# SaltwatersEchoCore.net
KiCad netlist of a schematic drawn in EAGLE
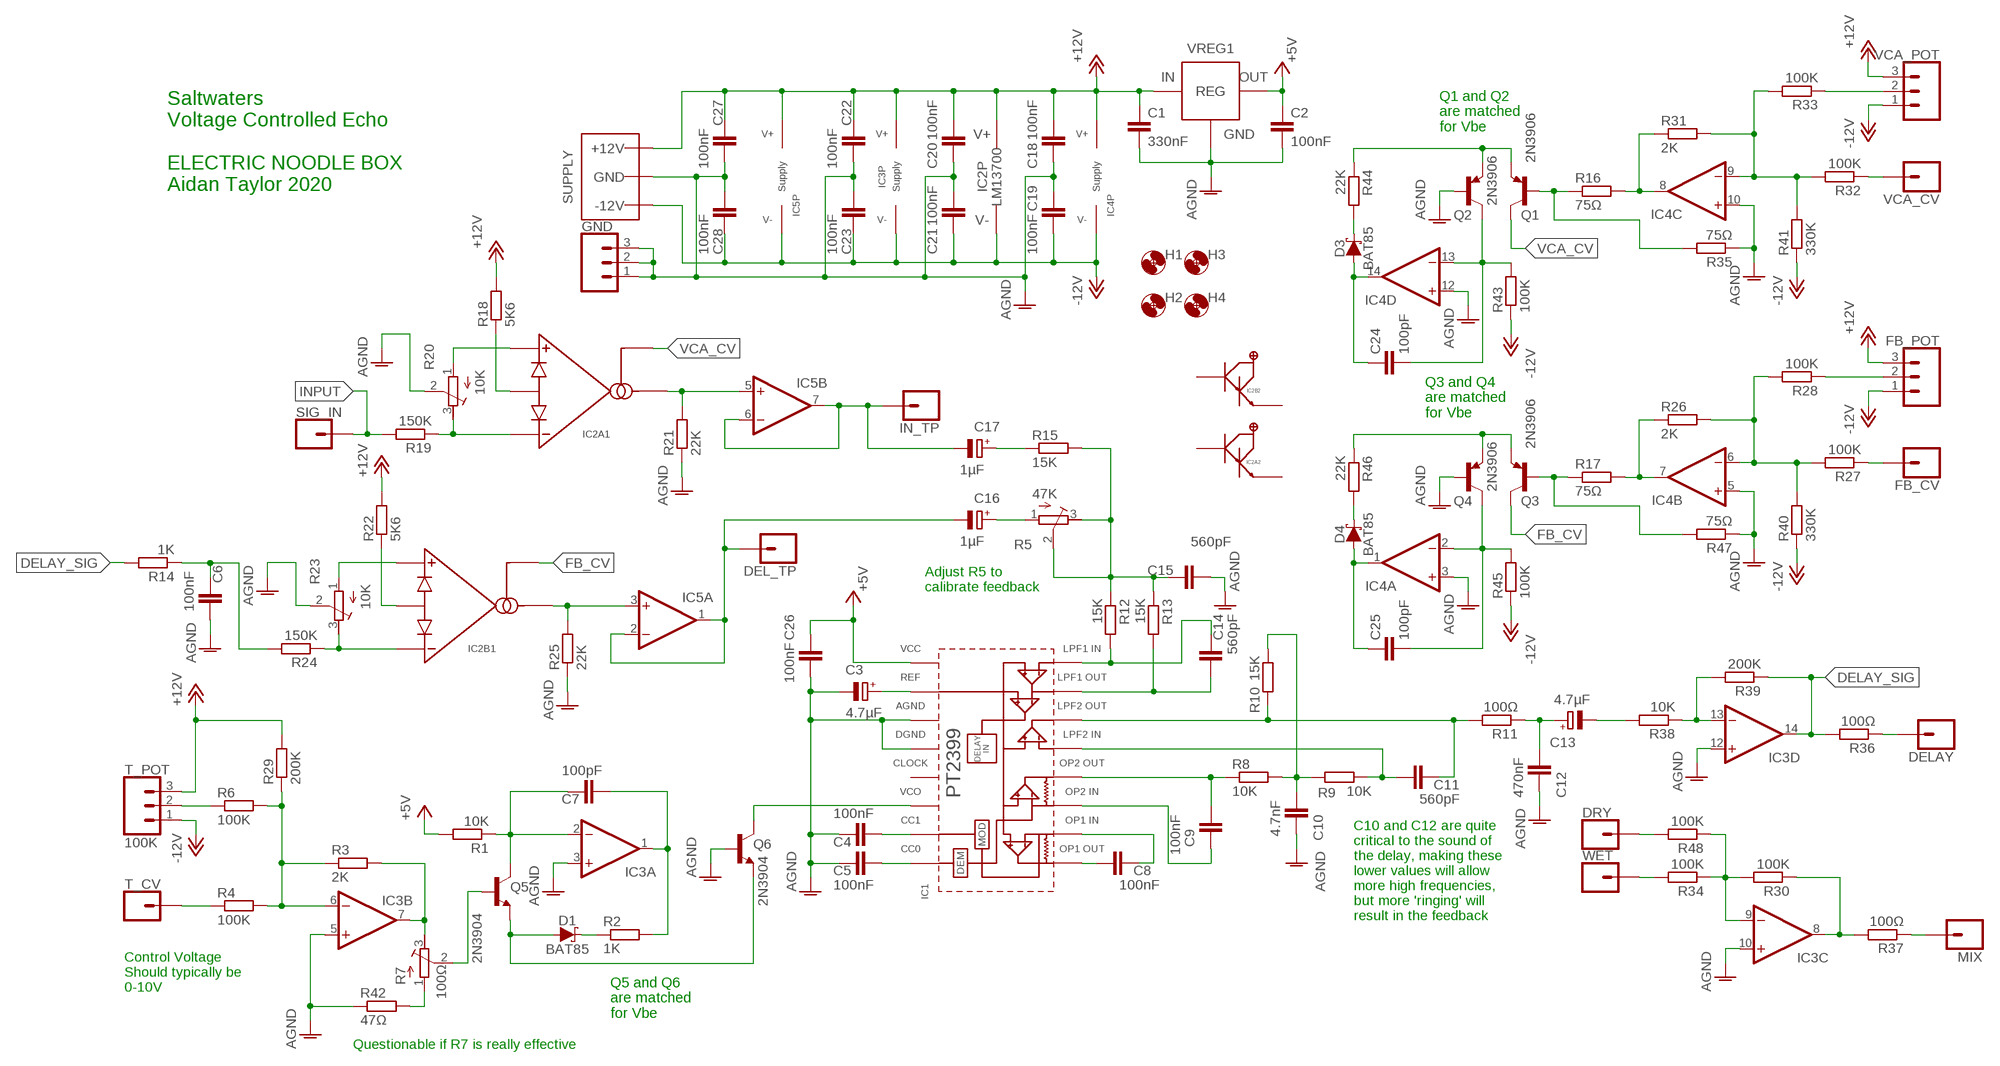
[diagram p0: schematic, sheet 1]

(export (version "E")
  (design (tool "Eeschema 10.0.6"))
  (components
    (comp (ref "C1")
      (value "330nF")
      (footprint "eagle-import:C050-025X075")
      (libsource (lib "eagle-import") (part "C-EU050-025X075"))
    )
    (comp (ref "C2")
      (value "100nF")
      (footprint "eagle-import:C050-025X075")
      (libsource (lib "eagle-import") (part "C-EU050-025X075"))
    )
    (comp (ref "C3")
      (value "4.7µF")
      (footprint "eagle-import:E2-5")
      (libsource (lib "eagle-import") (part "CPOL-EUE2-5"))
    )
    (comp (ref "C4")
      (value "100nF")
      (footprint "eagle-import:C050-025X075")
      (libsource (lib "eagle-import") (part "C-EU050-025X075"))
    )
    (comp (ref "C5")
      (value "100nF")
      (footprint "eagle-import:C050-025X075")
      (libsource (lib "eagle-import") (part "C-EU050-025X075"))
    )
    (comp (ref "C6")
      (value "100nF")
      (footprint "eagle-import:C050-025X075")
      (libsource (lib "eagle-import") (part "C-EU050-025X075"))
    )
    (comp (ref "C7")
      (value "100pF")
      (footprint "eagle-import:C050-025X075")
      (libsource (lib "eagle-import") (part "C-EU050-025X075"))
    )
    (comp (ref "C8")
      (value "100nF")
      (footprint "eagle-import:C050-025X075")
      (libsource (lib "eagle-import") (part "C-EU050-025X075"))
    )
    (comp (ref "C9")
      (value "100nF")
      (footprint "eagle-import:C050-025X075")
      (libsource (lib "eagle-import") (part "C-EU050-025X075"))
    )
    (comp (ref "C10")
      (value "4.7nF")
      (footprint "eagle-import:C050-025X075")
      (libsource (lib "eagle-import") (part "C-EU050-025X075"))
    )
    (comp (ref "C11")
      (value "560pF")
      (footprint "eagle-import:C050-025X075")
      (libsource (lib "eagle-import") (part "C-EU050-025X075"))
    )
    (comp (ref "C12")
      (value "470nF")
      (footprint "eagle-import:C050-025X075")
      (libsource (lib "eagle-import") (part "C-EU050-025X075"))
    )
    (comp (ref "C13")
      (value "4.7µF")
      (footprint "eagle-import:E2-5")
      (libsource (lib "eagle-import") (part "CPOL-EUE2-5"))
    )
    (comp (ref "C14")
      (value "560pF")
      (footprint "eagle-import:C050-025X075")
      (libsource (lib "eagle-import") (part "C-EU050-025X075"))
    )
    (comp (ref "C15")
      (value "560pF")
      (footprint "eagle-import:C050-025X075")
      (libsource (lib "eagle-import") (part "C-EU050-025X075"))
    )
    (comp (ref "C16")
      (value "1µF")
      (footprint "eagle-import:E2-5")
      (libsource (lib "eagle-import") (part "CPOL-EUE2-5"))
    )
    (comp (ref "C17")
      (value "1µF")
      (footprint "eagle-import:E2-5")
      (libsource (lib "eagle-import") (part "CPOL-EUE2-5"))
    )
    (comp (ref "C18")
      (value "100nF")
      (footprint "eagle-import:C050-025X075")
      (libsource (lib "eagle-import") (part "C-EU050-025X075"))
    )
    (comp (ref "C19")
      (value "100nF")
      (footprint "eagle-import:C050-025X075")
      (libsource (lib "eagle-import") (part "C-EU050-025X075"))
    )
    (comp (ref "C20")
      (value "100nF")
      (footprint "eagle-import:C050-025X075")
      (libsource (lib "eagle-import") (part "C-EU050-025X075"))
    )
    (comp (ref "C21")
      (value "100nF")
      (footprint "eagle-import:C050-025X075")
      (libsource (lib "eagle-import") (part "C-EU050-025X075"))
    )
    (comp (ref "C22")
      (value "100nF")
      (footprint "eagle-import:C050-025X075")
      (libsource (lib "eagle-import") (part "C-EU050-025X075"))
    )
    (comp (ref "C23")
      (value "100nF")
      (footprint "eagle-import:C050-025X075")
      (libsource (lib "eagle-import") (part "C-EU050-025X075"))
    )
    (comp (ref "C24")
      (value "100pF")
      (footprint "eagle-import:C050-025X075")
      (libsource (lib "eagle-import") (part "C-EU050-025X075"))
    )
    (comp (ref "C25")
      (value "100pF")
      (footprint "eagle-import:C050-025X075")
      (libsource (lib "eagle-import") (part "C-EU050-025X075"))
    )
    (comp (ref "C26")
      (value "100nF")
      (footprint "eagle-import:C050-025X075")
      (libsource (lib "eagle-import") (part "C-EU050-025X075"))
    )
    (comp (ref "C27")
      (value "100nF")
      (footprint "eagle-import:C050-025X075")
      (libsource (lib "eagle-import") (part "C-EU050-025X075"))
    )
    (comp (ref "C28")
      (value "100nF")
      (footprint "eagle-import:C050-025X075")
      (libsource (lib "eagle-import") (part "C-EU050-025X075"))
    )
    (comp (ref "D1")
      (value "BAT85")
      (footprint "eagle-import:DO35-7")
      (libsource (lib "eagle-import") (part "SCHOTTKY_DO35"))
    )
    (comp (ref "D3")
      (value "BAT85")
      (footprint "eagle-import:DO35-7")
      (libsource (lib "eagle-import") (part "SCHOTTKY_DO35"))
    )
    (comp (ref "D4")
      (value "BAT85")
      (footprint "eagle-import:DO35-7")
      (libsource (lib "eagle-import") (part "SCHOTTKY_DO35"))
    )
    (comp (ref "DELAY")
      (value "1XWIREPAD")
      (footprint "eagle-import:1X01")
      (libsource (lib "eagle-import") (part "1XWIREPAD"))
    )
    (comp (ref "DEL_TP")
      (value "1XWIREPAD")
      (footprint "eagle-import:1X01")
      (libsource (lib "eagle-import") (part "1XWIREPAD"))
    )
    (comp (ref "DRY")
      (value "1XWIREPAD")
      (footprint "eagle-import:1X01")
      (libsource (lib "eagle-import") (part "1XWIREPAD"))
    )
    (comp (ref "FB_CV")
      (value "1XWIREPAD")
      (footprint "eagle-import:1X01")
      (libsource (lib "eagle-import") (part "1XWIREPAD"))
    )
    (comp (ref "FB_POT")
      (value "3XWIREPAD")
      (footprint "eagle-import:1X03")
      (libsource (lib "eagle-import") (part "3XWIREPAD"))
    )
    (comp (ref "GND")
      (value "3XWIREPAD")
      (footprint "eagle-import:1X03")
      (libsource (lib "eagle-import") (part "3XWIREPAD"))
    )
    (comp (ref "H1")
      (value "MOUNT-HOLE3.2")
      (footprint "eagle-import:3,2")
      (libsource (lib "eagle-import") (part "MOUNT-HOLE3.2"))
    )
    (comp (ref "H2")
      (value "MOUNT-HOLE3.2")
      (footprint "eagle-import:3,2")
      (libsource (lib "eagle-import") (part "MOUNT-HOLE3.2"))
    )
    (comp (ref "H3")
      (value "MOUNT-HOLE3.2")
      (footprint "eagle-import:3,2")
      (libsource (lib "eagle-import") (part "MOUNT-HOLE3.2"))
    )
    (comp (ref "H4")
      (value "MOUNT-HOLE3.2")
      (footprint "eagle-import:3,2")
      (libsource (lib "eagle-import") (part "MOUNT-HOLE3.2"))
    )
    (comp (ref "IC1")
      (value "PT2399DIL16")
      (footprint "eagle-import:DIL16")
      (libsource (lib "eagle-import") (part "PT2399DIL16"))
    )
    (comp (ref "IC2")
      (value "LM13700DIL")
      (footprint "eagle-import:DIL16")
      (libsource (lib "eagle-import") (part "LM13700DIL"))
    )
    (comp (ref "IC3")
      (value "TL0X4DIL")
      (footprint "eagle-import:DIL14")
      (libsource (lib "eagle-import") (part "TL0X4DIL"))
    )
    (comp (ref "IC4")
      (value "TL0X4DIL")
      (footprint "eagle-import:DIL14")
      (libsource (lib "eagle-import") (part "TL0X4DIL"))
    )
    (comp (ref "IC5")
      (value "TL0X2DIL")
      (footprint "eagle-import:DIL08")
      (libsource (lib "eagle-import") (part "TL0X2DIL"))
    )
    (comp (ref "IN_TP")
      (value "1XWIREPAD")
      (footprint "eagle-import:1X01")
      (libsource (lib "eagle-import") (part "1XWIREPAD"))
    )
    (comp (ref "MIX")
      (value "1XWIREPAD")
      (footprint "eagle-import:1X01")
      (libsource (lib "eagle-import") (part "1XWIREPAD"))
    )
    (comp (ref "Q1")
      (value "2N3906")
      (footprint "eagle-import:TO92")
      (libsource (lib "eagle-import") (part "2N3906"))
    )
    (comp (ref "Q2")
      (value "2N3906")
      (footprint "eagle-import:TO92")
      (libsource (lib "eagle-import") (part "2N3906"))
    )
    (comp (ref "Q3")
      (value "2N3906")
      (footprint "eagle-import:TO92")
      (libsource (lib "eagle-import") (part "2N3906"))
    )
    (comp (ref "Q4")
      (value "2N3906")
      (footprint "eagle-import:TO92")
      (libsource (lib "eagle-import") (part "2N3906"))
    )
    (comp (ref "Q5")
      (value "2N3904")
      (footprint "eagle-import:TO92")
      (libsource (lib "eagle-import") (part "2N3904"))
    )
    (comp (ref "Q6")
      (value "2N3904")
      (footprint "eagle-import:TO92")
      (libsource (lib "eagle-import") (part "2N3904"))
    )
    (comp (ref "R1")
      (value "10K")
      (footprint "eagle-import:0207_10")
      (libsource (lib "eagle-import") (part "R-EU_0207/10"))
    )
    (comp (ref "R2")
      (value "1K")
      (footprint "eagle-import:0207_10")
      (libsource (lib "eagle-import") (part "R-EU_0207/10"))
    )
    (comp (ref "R3")
      (value "2K")
      (footprint "eagle-import:0207_10")
      (libsource (lib "eagle-import") (part "R-EU_0207/10"))
    )
    (comp (ref "R4")
      (value "100K")
      (footprint "eagle-import:0207_10")
      (libsource (lib "eagle-import") (part "R-EU_0207/10"))
    )
    (comp (ref "R5")
      (value "47K")
      (footprint "eagle-import:RTRIM3296W")
      (libsource (lib "eagle-import") (part "R-TRIMM3296W"))
    )
    (comp (ref "R6")
      (value "100K")
      (footprint "eagle-import:0207_10")
      (libsource (lib "eagle-import") (part "R-EU_0207/10"))
    )
    (comp (ref "R7")
      (value "100Ω")
      (footprint "eagle-import:RTRIM3296W")
      (libsource (lib "eagle-import") (part "R-TRIMM3296W"))
    )
    (comp (ref "R8")
      (value "10K")
      (footprint "eagle-import:0207_10")
      (libsource (lib "eagle-import") (part "R-EU_0207/10"))
    )
    (comp (ref "R9")
      (value "10K")
      (footprint "eagle-import:0207_10")
      (libsource (lib "eagle-import") (part "R-EU_0207/10"))
    )
    (comp (ref "R10")
      (value "15K")
      (footprint "eagle-import:0207_10")
      (libsource (lib "eagle-import") (part "R-EU_0207/10"))
    )
    (comp (ref "R11")
      (value "100Ω")
      (footprint "eagle-import:0207_10")
      (libsource (lib "eagle-import") (part "R-EU_0207/10"))
    )
    (comp (ref "R12")
      (value "15K")
      (footprint "eagle-import:0207_10")
      (libsource (lib "eagle-import") (part "R-EU_0207/10"))
    )
    (comp (ref "R13")
      (value "15K")
      (footprint "eagle-import:0207_10")
      (libsource (lib "eagle-import") (part "R-EU_0207/10"))
    )
    (comp (ref "R14")
      (value "1K")
      (footprint "eagle-import:0207_10")
      (libsource (lib "eagle-import") (part "R-EU_0207/10"))
    )
    (comp (ref "R15")
      (value "15K")
      (footprint "eagle-import:0207_10")
      (libsource (lib "eagle-import") (part "R-EU_0207/10"))
    )
    (comp (ref "R16")
      (value "75Ω")
      (footprint "eagle-import:0207_10")
      (libsource (lib "eagle-import") (part "R-EU_0207/10"))
    )
    (comp (ref "R17")
      (value "75Ω")
      (footprint "eagle-import:0207_10")
      (libsource (lib "eagle-import") (part "R-EU_0207/10"))
    )
    (comp (ref "R18")
      (value "5K6")
      (footprint "eagle-import:0207_10")
      (libsource (lib "eagle-import") (part "R-EU_0207/10"))
    )
    (comp (ref "R19")
      (value "150K")
      (footprint "eagle-import:0207_10")
      (libsource (lib "eagle-import") (part "R-EU_0207/10"))
    )
    (comp (ref "R20")
      (value "10K")
      (footprint "eagle-import:RTRIM3296W")
      (libsource (lib "eagle-import") (part "R-TRIMM3296W"))
    )
    (comp (ref "R21")
      (value "22K")
      (footprint "eagle-import:0207_10")
      (libsource (lib "eagle-import") (part "R-EU_0207/10"))
    )
    (comp (ref "R22")
      (value "5K6")
      (footprint "eagle-import:0207_10")
      (libsource (lib "eagle-import") (part "R-EU_0207/10"))
    )
    (comp (ref "R23")
      (value "10K")
      (footprint "eagle-import:RTRIM3296W")
      (libsource (lib "eagle-import") (part "R-TRIMM3296W"))
    )
    (comp (ref "R24")
      (value "150K")
      (footprint "eagle-import:0207_10")
      (libsource (lib "eagle-import") (part "R-EU_0207/10"))
    )
    (comp (ref "R25")
      (value "22K")
      (footprint "eagle-import:0207_10")
      (libsource (lib "eagle-import") (part "R-EU_0207/10"))
    )
    (comp (ref "R26")
      (value "2K")
      (footprint "eagle-import:0207_10")
      (libsource (lib "eagle-import") (part "R-EU_0207/10"))
    )
    (comp (ref "R27")
      (value "100K")
      (footprint "eagle-import:0207_10")
      (libsource (lib "eagle-import") (part "R-EU_0207/10"))
    )
    (comp (ref "R28")
      (value "100K")
      (footprint "eagle-import:0207_10")
      (libsource (lib "eagle-import") (part "R-EU_0207/10"))
    )
    (comp (ref "R29")
      (value "200K")
      (footprint "eagle-import:0207_10")
      (libsource (lib "eagle-import") (part "R-EU_0207/10"))
    )
    (comp (ref "R30")
      (value "100K")
      (footprint "eagle-import:0207_10")
      (libsource (lib "eagle-import") (part "R-EU_0207/10"))
    )
    (comp (ref "R31")
      (value "2K")
      (footprint "eagle-import:0207_10")
      (libsource (lib "eagle-import") (part "R-EU_0207/10"))
    )
    (comp (ref "R32")
      (value "100K")
      (footprint "eagle-import:0207_10")
      (libsource (lib "eagle-import") (part "R-EU_0207/10"))
    )
    (comp (ref "R33")
      (value "100K")
      (footprint "eagle-import:0207_10")
      (libsource (lib "eagle-import") (part "R-EU_0207/10"))
    )
    (comp (ref "R34")
      (value "100K")
      (footprint "eagle-import:0207_10")
      (libsource (lib "eagle-import") (part "R-EU_0207/10"))
    )
    (comp (ref "R35")
      (value "75Ω")
      (footprint "eagle-import:0207_10")
      (libsource (lib "eagle-import") (part "R-EU_0207/10"))
    )
    (comp (ref "R36")
      (value "100Ω")
      (footprint "eagle-import:0207_10")
      (libsource (lib "eagle-import") (part "R-EU_0207/10"))
    )
    (comp (ref "R37")
      (value "100Ω")
      (footprint "eagle-import:0207_10")
      (libsource (lib "eagle-import") (part "R-EU_0207/10"))
    )
    (comp (ref "R38")
      (value "10K")
      (footprint "eagle-import:0207_10")
      (libsource (lib "eagle-import") (part "R-EU_0207/10"))
    )
    (comp (ref "R39")
      (value "200K")
      (footprint "eagle-import:0207_10")
      (libsource (lib "eagle-import") (part "R-EU_0207/10"))
    )
    (comp (ref "R40")
      (value "330K")
      (footprint "eagle-import:0207_10")
      (libsource (lib "eagle-import") (part "R-EU_0207/10"))
    )
    (comp (ref "R41")
      (value "330K")
      (footprint "eagle-import:0207_10")
      (libsource (lib "eagle-import") (part "R-EU_0207/10"))
    )
    (comp (ref "R42")
      (value "47Ω")
      (footprint "eagle-import:0207_10")
      (libsource (lib "eagle-import") (part "R-EU_0207/10"))
    )
    (comp (ref "R43")
      (value "100K")
      (footprint "eagle-import:0207_10")
      (libsource (lib "eagle-import") (part "R-EU_0207/10"))
    )
    (comp (ref "R44")
      (value "22K")
      (footprint "eagle-import:0207_10")
      (libsource (lib "eagle-import") (part "R-EU_0207/10"))
    )
    (comp (ref "R45")
      (value "100K")
      (footprint "eagle-import:0207_10")
      (libsource (lib "eagle-import") (part "R-EU_0207/10"))
    )
    (comp (ref "R46")
      (value "22K")
      (footprint "eagle-import:0207_10")
      (libsource (lib "eagle-import") (part "R-EU_0207/10"))
    )
    (comp (ref "R47")
      (value "75Ω")
      (footprint "eagle-import:0207_10")
      (libsource (lib "eagle-import") (part "R-EU_0207/10"))
    )
    (comp (ref "R48")
      (value "100K")
      (footprint "eagle-import:0207_10")
      (libsource (lib "eagle-import") (part "R-EU_0207/10"))
    )
    (comp (ref "SIG_IN")
      (value "1XWIREPAD")
      (footprint "eagle-import:1X01")
      (libsource (lib "eagle-import") (part "1XWIREPAD"))
    )
    (comp (ref "T_CV")
      (value "1XWIREPAD")
      (footprint "eagle-import:1X01")
      (libsource (lib "eagle-import") (part "1XWIREPAD"))
    )
    (comp (ref "T_POT")
      (value "100K")
      (footprint "eagle-import:1X03")
      (libsource (lib "eagle-import") (part "3XWIREPAD"))
    )
    (comp (ref "VCA_CV")
      (value "1XWIREPAD")
      (footprint "eagle-import:1X01")
      (libsource (lib "eagle-import") (part "1XWIREPAD"))
    )
    (comp (ref "VCA_POT")
      (value "3XWIREPAD")
      (footprint "eagle-import:1X03")
      (libsource (lib "eagle-import") (part "3XWIREPAD"))
    )
    (comp (ref "VREG1")
      (value "L78L05TO92")
      (footprint "eagle-import:TO92")
      (libsource (lib "eagle-import") (part "L78L05TO92"))
    )
    (comp (ref "WET")
      (value "1XWIREPAD")
      (footprint "eagle-import:1X01")
      (libsource (lib "eagle-import") (part "1XWIREPAD"))
    )
    (comp (ref "WP1")
      (value "COMBO_SUPPLY_HEADER")
      (footprint "eagle-import:COMBINED_POWER")
      (libsource (lib "eagle-import") (part "COMBO_SUPPLY_HEADER"))
    )
  )
  (nets
    (net (code "1") (name "+5V") (class "Default")
      (node (ref "C2") (pin "1") (pinfunction "1_1") (pintype "passive"))
      (node (ref "C26") (pin "1") (pinfunction "1_1") (pintype "passive"))
      (node (ref "IC1") (pin "1") (pinfunction "VCC_1") (pintype "power_in"))
      (node (ref "R1") (pin "2") (pinfunction "2_2") (pintype "passive"))
      (node (ref "VREG1") (pin "1") (pinfunction "VOUT_1") (pintype "output"))
    )
    (net (code "2") (name "+12V") (class "Default")
      (node (ref "C1") (pin "1") (pinfunction "1_1") (pintype "passive"))
      (node (ref "C18") (pin "2") (pinfunction "2_2") (pintype "passive"))
      (node (ref "C20") (pin "2") (pinfunction "2_2") (pintype "passive"))
      (node (ref "C22") (pin "2") (pinfunction "2_2") (pintype "passive"))
      (node (ref "C27") (pin "2") (pinfunction "2_2") (pintype "passive"))
      (node (ref "FB_POT") (pin "3") (pinfunction "3_3") (pintype "passive"))
      (node (ref "IC2") (pin "11") (pinfunction "V+_11") (pintype "power_in"))
      (node (ref "IC3") (pin "4") (pinfunction "V+_4") (pintype "bidirectional"))
      (node (ref "IC4") (pin "4") (pinfunction "V+_4") (pintype "bidirectional"))
      (node (ref "IC5") (pin "8") (pinfunction "V+_8") (pintype "bidirectional"))
      (node (ref "R18") (pin "2") (pinfunction "2_2") (pintype "passive"))
      (node (ref "R22") (pin "2") (pinfunction "2_2") (pintype "passive"))
      (node (ref "R29") (pin "2") (pinfunction "2_2") (pintype "passive"))
      (node (ref "T_POT") (pin "3") (pinfunction "3_3") (pintype "passive"))
      (node (ref "VCA_POT") (pin "3") (pinfunction "3_3") (pintype "passive"))
      (node (ref "VREG1") (pin "3") (pinfunction "VIN_3") (pintype "input"))
      (node (ref "WP1") (pin "V+1") (pinfunction "V++_V+1") (pintype "power_in"))
      (node (ref "WP1") (pin "V+2") (pinfunction "V++_V+2") (pintype "power_in"))
      (node (ref "WP1") (pin "V+3") (pinfunction "V++_V+3") (pintype "power_in"))
    )
    (net (code "3") (name "-12V") (class "Default")
      (node (ref "C19") (pin "1") (pinfunction "1_1") (pintype "passive"))
      (node (ref "C21") (pin "1") (pinfunction "1_1") (pintype "passive"))
      (node (ref "C23") (pin "1") (pinfunction "1_1") (pintype "passive"))
      (node (ref "C28") (pin "1") (pinfunction "1_1") (pintype "passive"))
      (node (ref "FB_POT") (pin "1") (pinfunction "1_1") (pintype "passive"))
      (node (ref "IC2") (pin "6") (pinfunction "V-_6") (pintype "power_in"))
      (node (ref "IC3") (pin "11") (pinfunction "V-_11") (pintype "bidirectional"))
      (node (ref "IC4") (pin "11") (pinfunction "V-_11") (pintype "bidirectional"))
      (node (ref "IC5") (pin "4") (pinfunction "V-_4") (pintype "bidirectional"))
      (node (ref "R40") (pin "1") (pinfunction "1_1") (pintype "passive"))
      (node (ref "R41") (pin "1") (pinfunction "1_1") (pintype "passive"))
      (node (ref "R43") (pin "1") (pinfunction "1_1") (pintype "passive"))
      (node (ref "R45") (pin "1") (pinfunction "1_1") (pintype "passive"))
      (node (ref "T_POT") (pin "1") (pinfunction "1_1") (pintype "passive"))
      (node (ref "VCA_POT") (pin "1") (pinfunction "1_1") (pintype "passive"))
      (node (ref "WP1") (pin "V-1") (pinfunction "V--_V-1") (pintype "power_in"))
      (node (ref "WP1") (pin "V-2") (pinfunction "V--_V-2") (pintype "power_in"))
      (node (ref "WP1") (pin "V-3") (pinfunction "V--_V-3") (pintype "power_in"))
    )
    (net (code "4") (name "AGND") (class "Default")
      (node (ref "C1") (pin "2") (pinfunction "2_2") (pintype "passive"))
      (node (ref "C10") (pin "1") (pinfunction "1_1") (pintype "passive"))
      (node (ref "C12") (pin "1") (pinfunction "1_1") (pintype "passive"))
      (node (ref "C15") (pin "2") (pinfunction "2_2") (pintype "passive"))
      (node (ref "C18") (pin "1") (pinfunction "1_1") (pintype "passive"))
      (node (ref "C19") (pin "2") (pinfunction "2_2") (pintype "passive"))
      (node (ref "C2") (pin "2") (pinfunction "2_2") (pintype "passive"))
      (node (ref "C20") (pin "1") (pinfunction "1_1") (pintype "passive"))
      (node (ref "C21") (pin "2") (pinfunction "2_2") (pintype "passive"))
      (node (ref "C22") (pin "1") (pinfunction "1_1") (pintype "passive"))
      (node (ref "C23") (pin "2") (pinfunction "2_2") (pintype "passive"))
      (node (ref "C26") (pin "2") (pinfunction "2_2") (pintype "passive"))
      (node (ref "C27") (pin "1") (pinfunction "1_1") (pintype "passive"))
      (node (ref "C28") (pin "2") (pinfunction "2_2") (pintype "passive"))
      (node (ref "C3") (pin "-") (pinfunction "-_-") (pintype "passive"))
      (node (ref "C4") (pin "2") (pinfunction "2_2") (pintype "passive"))
      (node (ref "C5") (pin "2") (pinfunction "2_2") (pintype "passive"))
      (node (ref "C6") (pin "2") (pinfunction "2_2") (pintype "passive"))
      (node (ref "GND") (pin "1") (pinfunction "1_1") (pintype "passive"))
      (node (ref "GND") (pin "2") (pinfunction "2_2") (pintype "passive"))
      (node (ref "GND") (pin "3") (pinfunction "3_3") (pintype "passive"))
      (node (ref "IC1") (pin "3") (pinfunction "AGND_3") (pintype "power_in"))
      (node (ref "IC1") (pin "4") (pinfunction "DGND_4") (pintype "power_in"))
      (node (ref "IC3") (pin "10") (pinfunction "+IN_10") (pintype "input"))
      (node (ref "IC3") (pin "12") (pinfunction "+IN_12") (pintype "input"))
      (node (ref "IC3") (pin "3") (pinfunction "+IN_3") (pintype "input"))
      (node (ref "IC3") (pin "5") (pinfunction "+IN_5") (pintype "input"))
      (node (ref "IC4") (pin "10") (pinfunction "+IN_10") (pintype "input"))
      (node (ref "IC4") (pin "12") (pinfunction "+IN_12") (pintype "input"))
      (node (ref "IC4") (pin "3") (pinfunction "+IN_3") (pintype "input"))
      (node (ref "IC4") (pin "5") (pinfunction "+IN_5") (pintype "input"))
      (node (ref "Q2") (pin "2") (pinfunction "B_2") (pintype "passive"))
      (node (ref "Q4") (pin "2") (pinfunction "B_2") (pintype "passive"))
      (node (ref "Q6") (pin "2") (pinfunction "B_2") (pintype "passive"))
      (node (ref "R20") (pin "2") (pinfunction "S_2") (pintype "passive"))
      (node (ref "R21") (pin "1") (pinfunction "1_1") (pintype "passive"))
      (node (ref "R23") (pin "2") (pinfunction "S_2") (pintype "passive"))
      (node (ref "R25") (pin "1") (pinfunction "1_1") (pintype "passive"))
      (node (ref "R35") (pin "1") (pinfunction "1_1") (pintype "passive"))
      (node (ref "R42") (pin "1") (pinfunction "1_1") (pintype "passive"))
      (node (ref "R47") (pin "1") (pinfunction "1_1") (pintype "passive"))
      (node (ref "VREG1") (pin "2") (pinfunction "GND_2") (pintype "power_in"))
      (node (ref "WP1") (pin "GND1") (pinfunction "AGND_GND1") (pintype "power_in"))
      (node (ref "WP1") (pin "GND2") (pinfunction "AGND_GND2") (pintype "power_in"))
      (node (ref "WP1") (pin "GND3") (pinfunction "AGND_GND3") (pintype "power_in"))
      (node (ref "WP1") (pin "GND4") (pinfunction "AGND_GND4") (pintype "power_in"))
      (node (ref "WP1") (pin "GND5") (pinfunction "AGND_GND5") (pintype "power_in"))
      (node (ref "WP1") (pin "GND6") (pinfunction "AGND_GND6") (pintype "power_in"))
      (node (ref "WP1") (pin "GND7") (pinfunction "AGND_GND7") (pintype "power_in"))
      (node (ref "WP1") (pin "GND8") (pinfunction "AGND_GND8") (pintype "power_in"))
    )
    (net (code "5") (name "DELAY_SIG") (class "Default")
      (node (ref "IC3") (pin "14") (pinfunction "OUT_14") (pintype "output"))
      (node (ref "R14") (pin "2") (pinfunction "2_2") (pintype "passive"))
      (node (ref "R36") (pin "2") (pinfunction "2_2") (pintype "passive"))
      (node (ref "R39") (pin "1") (pinfunction "1_1") (pintype "passive"))
    )
    (net (code "6") (name "FB_CV") (class "Default")
      (node (ref "IC2") (pin "16") (pinfunction "AMPBIAS_16") (pintype "input"))
      (node (ref "Q3") (pin "1") (pinfunction "C_1") (pintype "passive"))
    )
    (net (code "7") (name "INPUT") (class "Default")
      (node (ref "R19") (pin "2") (pinfunction "2_2") (pintype "passive"))
      (node (ref "SIG_IN") (pin "1") (pinfunction "1_1") (pintype "passive"))
    )
    (net (code "8") (name "Net-(C6-Pad1)") (class "Default")
      (node (ref "C6") (pin "1") (pinfunction "1_1") (pintype "passive"))
      (node (ref "R14") (pin "1") (pinfunction "1_1") (pintype "passive"))
      (node (ref "R24") (pin "2") (pinfunction "2_2") (pintype "passive"))
    )
    (net (code "9") (name "Net-(C10-Pad2)") (class "Default")
      (node (ref "C10") (pin "2") (pinfunction "2_2") (pintype "passive"))
      (node (ref "R10") (pin "1") (pinfunction "1_1") (pintype "passive"))
      (node (ref "R8") (pin "2") (pinfunction "2_2") (pintype "passive"))
      (node (ref "R9") (pin "2") (pinfunction "2_2") (pintype "passive"))
    )
    (net (code "10") (name "Net-(C12-Pad2)") (class "Default")
      (node (ref "C12") (pin "2") (pinfunction "2_2") (pintype "passive"))
      (node (ref "C13") (pin "+") (pinfunction "+_+") (pintype "passive"))
      (node (ref "R11") (pin "1") (pinfunction "1_1") (pintype "passive"))
    )
    (net (code "11") (name "Net-(C13-Pad-)") (class "Default")
      (node (ref "C13") (pin "-") (pinfunction "-_-") (pintype "passive"))
      (node (ref "R38") (pin "2") (pinfunction "2_2") (pintype "passive"))
    )
    (net (code "12") (name "Net-(C17-Pad+)") (class "Default")
      (node (ref "C17") (pin "+") (pinfunction "+_+") (pintype "passive"))
      (node (ref "R15") (pin "1") (pinfunction "1_1") (pintype "passive"))
    )
    (net (code "13") (name "Net-(D1-PadC)") (class "Default")
      (node (ref "D1") (pin "C") (pinfunction "C_C") (pintype "passive"))
      (node (ref "R2") (pin "1") (pinfunction "1_1") (pintype "passive"))
    )
    (net (code "14") (name "Net-(D3-PadC)") (class "Default")
      (node (ref "D3") (pin "C") (pinfunction "C_C") (pintype "passive"))
      (node (ref "R44") (pin "2") (pinfunction "2_2") (pintype "passive"))
    )
    (net (code "15") (name "Net-(D4-PadC)") (class "Default")
      (node (ref "D4") (pin "C") (pinfunction "C_C") (pintype "passive"))
      (node (ref "R46") (pin "2") (pinfunction "2_2") (pintype "passive"))
    )
    (net (code "16") (name "Net-(DELAY-Pad1)") (class "Default")
      (node (ref "DELAY") (pin "1") (pinfunction "1_1") (pintype "passive"))
      (node (ref "R36") (pin "1") (pinfunction "1_1") (pintype "passive"))
    )
    (net (code "17") (name "Net-(DRY-Pad1)") (class "Default")
      (node (ref "DRY") (pin "1") (pinfunction "1_1") (pintype "passive"))
      (node (ref "R48") (pin "2") (pinfunction "2_2") (pintype "passive"))
    )
    (net (code "18") (name "Net-(FB_CV-Pad1)") (class "Default")
      (node (ref "FB_CV") (pin "1") (pinfunction "1_1") (pintype "passive"))
      (node (ref "R27") (pin "1") (pinfunction "1_1") (pintype "passive"))
    )
    (net (code "19") (name "Net-(FB_POT-Pad2)") (class "Default")
      (node (ref "FB_POT") (pin "2") (pinfunction "2_2") (pintype "passive"))
      (node (ref "R28") (pin "1") (pinfunction "1_1") (pintype "passive"))
    )
    (net (code "20") (name "Net-(IC1-CC0)") (class "Default")
      (node (ref "C5") (pin "1") (pinfunction "1_1") (pintype "passive"))
      (node (ref "IC1") (pin "8") (pinfunction "CC0_8") (pintype "input"))
    )
    (net (code "21") (name "Net-(IC1-CC1)") (class "Default")
      (node (ref "C4") (pin "1") (pinfunction "1_1") (pintype "passive"))
      (node (ref "IC1") (pin "7") (pinfunction "CC1_7") (pintype "input"))
    )
    (net (code "22") (name "Net-(IC1-LPF1_IN)") (class "Default")
      (node (ref "C14") (pin "1") (pinfunction "1_1") (pintype "passive"))
      (node (ref "IC1") (pin "16") (pinfunction "LPF1_IN_16") (pintype "input"))
      (node (ref "R12") (pin "2") (pinfunction "2_2") (pintype "passive"))
    )
    (net (code "23") (name "Net-(IC1-LPF1_OUT)") (class "Default")
      (node (ref "C14") (pin "2") (pinfunction "2_2") (pintype "passive"))
      (node (ref "IC1") (pin "15") (pinfunction "LPF1_OUT_15") (pintype "output"))
      (node (ref "R13") (pin "2") (pinfunction "2_2") (pintype "passive"))
    )
    (net (code "24") (name "Net-(IC1-LPF2_IN)") (class "Default")
      (node (ref "C11") (pin "2") (pinfunction "2_2") (pintype "passive"))
      (node (ref "IC1") (pin "13") (pinfunction "LPF2_IN_13") (pintype "input"))
      (node (ref "R9") (pin "1") (pinfunction "1_1") (pintype "passive"))
    )
    (net (code "25") (name "Net-(IC1-LPF2_OUT)") (class "Default")
      (node (ref "C11") (pin "1") (pinfunction "1_1") (pintype "passive"))
      (node (ref "IC1") (pin "14") (pinfunction "LPF2_OUT_14") (pintype "output"))
      (node (ref "R10") (pin "2") (pinfunction "2_2") (pintype "passive"))
      (node (ref "R11") (pin "2") (pinfunction "2_2") (pintype "passive"))
    )
    (net (code "26") (name "Net-(IC1-OP1_IN)") (class "Default")
      (node (ref "C8") (pin "1") (pinfunction "1_1") (pintype "passive"))
      (node (ref "IC1") (pin "10") (pinfunction "OP1_IN_10") (pintype "input"))
    )
    (net (code "27") (name "Net-(IC1-OP1_OUT)") (class "Default")
      (node (ref "C8") (pin "2") (pinfunction "2_2") (pintype "passive"))
      (node (ref "IC1") (pin "9") (pinfunction "OP1_OUT_9") (pintype "output"))
    )
    (net (code "28") (name "Net-(IC1-OP2_IN)") (class "Default")
      (node (ref "C9") (pin "1") (pinfunction "1_1") (pintype "passive"))
      (node (ref "IC1") (pin "11") (pinfunction "OP2_IN_11") (pintype "input"))
    )
    (net (code "29") (name "Net-(IC1-OP2_OUT)") (class "Default")
      (node (ref "C9") (pin "2") (pinfunction "2_2") (pintype "passive"))
      (node (ref "IC1") (pin "12") (pinfunction "OP2_OUT_12") (pintype "output"))
      (node (ref "R8") (pin "1") (pinfunction "1_1") (pintype "passive"))
    )
    (net (code "30") (name "Net-(IC1-REF)") (class "Default")
      (node (ref "C3") (pin "+") (pinfunction "+_+") (pintype "passive"))
      (node (ref "IC1") (pin "2") (pinfunction "REF_2") (pintype "power_in"))
    )
    (net (code "31") (name "Net-(IC1-VCO)") (class "Default")
      (node (ref "IC1") (pin "6") (pinfunction "VCO_6") (pintype "input"))
      (node (ref "Q6") (pin "1") (pinfunction "C_1") (pintype "passive"))
    )
    (net (code "32") (name "Net-(IC2A-AMP+)") (class "Default")
      (node (ref "IC2") (pin "3") (pinfunction "AMP+_3") (pintype "input"))
      (node (ref "R20") (pin "1") (pinfunction "A_1") (pintype "passive"))
    )
    (net (code "33") (name "Net-(IC2A-AMP-)") (class "Default")
      (node (ref "IC2") (pin "4") (pinfunction "AMP-_4") (pintype "input"))
      (node (ref "R19") (pin "1") (pinfunction "1_1") (pintype "passive"))
      (node (ref "R20") (pin "3") (pinfunction "E_3") (pintype "passive"))
    )
    (net (code "34") (name "Net-(IC2A-AMPOUT)") (class "Default")
      (node (ref "IC2") (pin "5") (pinfunction "AMPOUT_5") (pintype "output"))
      (node (ref "IC5") (pin "5") (pinfunction "+IN_5") (pintype "input"))
      (node (ref "R21") (pin "2") (pinfunction "2_2") (pintype "passive"))
    )
    (net (code "35") (name "Net-(IC2A-DIODES)") (class "Default")
      (node (ref "IC2") (pin "2") (pinfunction "DIODES_2") (pintype "input"))
      (node (ref "R18") (pin "1") (pinfunction "1_1") (pintype "passive"))
    )
    (net (code "36") (name "Net-(IC2C-AMP+)") (class "Default")
      (node (ref "IC2") (pin "14") (pinfunction "AMP+_14") (pintype "input"))
      (node (ref "R23") (pin "1") (pinfunction "A_1") (pintype "passive"))
    )
    (net (code "37") (name "Net-(IC2C-AMP-)") (class "Default")
      (node (ref "IC2") (pin "13") (pinfunction "AMP-_13") (pintype "input"))
      (node (ref "R23") (pin "3") (pinfunction "E_3") (pintype "passive"))
      (node (ref "R24") (pin "1") (pinfunction "1_1") (pintype "passive"))
    )
    (net (code "38") (name "Net-(IC2C-AMPOUT)") (class "Default")
      (node (ref "IC2") (pin "12") (pinfunction "AMPOUT_12") (pintype "output"))
      (node (ref "IC5") (pin "3") (pinfunction "+IN_3") (pintype "input"))
      (node (ref "R25") (pin "2") (pinfunction "2_2") (pintype "passive"))
    )
    (net (code "39") (name "Net-(IC2C-DIODES)") (class "Default")
      (node (ref "IC2") (pin "15") (pinfunction "DIODES_15") (pintype "input"))
      (node (ref "R22") (pin "1") (pinfunction "1_1") (pintype "passive"))
    )
    (net (code "40") (name "Net-(IC3A--IN)") (class "Default")
      (node (ref "C7") (pin "2") (pinfunction "2_2") (pintype "passive"))
      (node (ref "IC3") (pin "2") (pinfunction "-IN_2") (pintype "input"))
      (node (ref "Q5") (pin "1") (pinfunction "C_1") (pintype "passive"))
      (node (ref "R1") (pin "1") (pinfunction "1_1") (pintype "passive"))
    )
    (net (code "41") (name "Net-(IC3A-OUT)") (class "Default")
      (node (ref "C7") (pin "1") (pinfunction "1_1") (pintype "passive"))
      (node (ref "IC3") (pin "1") (pinfunction "OUT_1") (pintype "output"))
      (node (ref "R2") (pin "2") (pinfunction "2_2") (pintype "passive"))
    )
    (net (code "42") (name "Net-(IC3B--IN)") (class "Default")
      (node (ref "IC3") (pin "6") (pinfunction "-IN_6") (pintype "input"))
      (node (ref "R29") (pin "1") (pinfunction "1_1") (pintype "passive"))
      (node (ref "R3") (pin "1") (pinfunction "1_1") (pintype "passive"))
      (node (ref "R4") (pin "2") (pinfunction "2_2") (pintype "passive"))
      (node (ref "R6") (pin "2") (pinfunction "2_2") (pintype "passive"))
    )
    (net (code "43") (name "Net-(IC3B-OUT)") (class "Default")
      (node (ref "IC3") (pin "7") (pinfunction "OUT_7") (pintype "output"))
      (node (ref "R3") (pin "2") (pinfunction "2_2") (pintype "passive"))
      (node (ref "R7") (pin "3") (pinfunction "E_3") (pintype "passive"))
    )
    (net (code "44") (name "Net-(IC3C--IN)") (class "Default")
      (node (ref "IC3") (pin "9") (pinfunction "-IN_9") (pintype "input"))
      (node (ref "R30") (pin "2") (pinfunction "2_2") (pintype "passive"))
      (node (ref "R34") (pin "1") (pinfunction "1_1") (pintype "passive"))
      (node (ref "R48") (pin "1") (pinfunction "1_1") (pintype "passive"))
    )
    (net (code "45") (name "Net-(IC3C-OUT)") (class "Default")
      (node (ref "IC3") (pin "8") (pinfunction "OUT_8") (pintype "output"))
      (node (ref "R30") (pin "1") (pinfunction "1_1") (pintype "passive"))
      (node (ref "R37") (pin "2") (pinfunction "2_2") (pintype "passive"))
    )
    (net (code "46") (name "Net-(IC3D--IN)") (class "Default")
      (node (ref "IC3") (pin "13") (pinfunction "-IN_13") (pintype "input"))
      (node (ref "R38") (pin "1") (pinfunction "1_1") (pintype "passive"))
      (node (ref "R39") (pin "2") (pinfunction "2_2") (pintype "passive"))
    )
    (net (code "47") (name "Net-(IC4A--IN)") (class "Default")
      (node (ref "C25") (pin "2") (pinfunction "2_2") (pintype "passive"))
      (node (ref "IC4") (pin "2") (pinfunction "-IN_2") (pintype "input"))
      (node (ref "Q4") (pin "1") (pinfunction "C_1") (pintype "passive"))
      (node (ref "R45") (pin "2") (pinfunction "2_2") (pintype "passive"))
    )
    (net (code "48") (name "Net-(IC4A-OUT)") (class "Default")
      (node (ref "C25") (pin "1") (pinfunction "1_1") (pintype "passive"))
      (node (ref "D4") (pin "A") (pinfunction "A_A") (pintype "passive"))
      (node (ref "IC4") (pin "1") (pinfunction "OUT_1") (pintype "output"))
    )
    (net (code "49") (name "Net-(IC4B--IN)") (class "Default")
      (node (ref "IC4") (pin "6") (pinfunction "-IN_6") (pintype "input"))
      (node (ref "R26") (pin "2") (pinfunction "2_2") (pintype "passive"))
      (node (ref "R27") (pin "2") (pinfunction "2_2") (pintype "passive"))
      (node (ref "R28") (pin "2") (pinfunction "2_2") (pintype "passive"))
      (node (ref "R40") (pin "2") (pinfunction "2_2") (pintype "passive"))
    )
    (net (code "50") (name "Net-(IC4B-OUT)") (class "Default")
      (node (ref "IC4") (pin "7") (pinfunction "OUT_7") (pintype "output"))
      (node (ref "R17") (pin "2") (pinfunction "2_2") (pintype "passive"))
      (node (ref "R26") (pin "1") (pinfunction "1_1") (pintype "passive"))
    )
    (net (code "51") (name "Net-(IC4C--IN)") (class "Default")
      (node (ref "IC4") (pin "9") (pinfunction "-IN_9") (pintype "input"))
      (node (ref "R31") (pin "2") (pinfunction "2_2") (pintype "passive"))
      (node (ref "R32") (pin "2") (pinfunction "2_2") (pintype "passive"))
      (node (ref "R33") (pin "2") (pinfunction "2_2") (pintype "passive"))
      (node (ref "R41") (pin "2") (pinfunction "2_2") (pintype "passive"))
    )
    (net (code "52") (name "Net-(IC4C-OUT)") (class "Default")
      (node (ref "IC4") (pin "8") (pinfunction "OUT_8") (pintype "output"))
      (node (ref "R16") (pin "2") (pinfunction "2_2") (pintype "passive"))
      (node (ref "R31") (pin "1") (pinfunction "1_1") (pintype "passive"))
    )
    (net (code "53") (name "Net-(IC4D--IN)") (class "Default")
      (node (ref "C24") (pin "2") (pinfunction "2_2") (pintype "passive"))
      (node (ref "IC4") (pin "13") (pinfunction "-IN_13") (pintype "input"))
      (node (ref "Q2") (pin "1") (pinfunction "C_1") (pintype "passive"))
      (node (ref "R43") (pin "2") (pinfunction "2_2") (pintype "passive"))
    )
    (net (code "54") (name "Net-(IC4D-OUT)") (class "Default")
      (node (ref "C24") (pin "1") (pinfunction "1_1") (pintype "passive"))
      (node (ref "D3") (pin "A") (pinfunction "A_A") (pintype "passive"))
      (node (ref "IC4") (pin "14") (pinfunction "OUT_14") (pintype "output"))
    )
    (net (code "55") (name "Net-(IC5A--IN)") (class "Default")
      (node (ref "C16") (pin "-") (pinfunction "-_-") (pintype "passive"))
      (node (ref "DEL_TP") (pin "1") (pinfunction "1_1") (pintype "passive"))
      (node (ref "IC5") (pin "1") (pinfunction "OUT_1") (pintype "output"))
      (node (ref "IC5") (pin "2") (pinfunction "-IN_2") (pintype "input"))
    )
    (net (code "56") (name "Net-(IC5B--IN)") (class "Default")
      (node (ref "C17") (pin "-") (pinfunction "-_-") (pintype "passive"))
      (node (ref "IC5") (pin "6") (pinfunction "-IN_6") (pintype "input"))
      (node (ref "IC5") (pin "7") (pinfunction "OUT_7") (pintype "output"))
      (node (ref "IN_TP") (pin "1") (pinfunction "1_1") (pintype "passive"))
    )
    (net (code "57") (name "Net-(MIX-Pad1)") (class "Default")
      (node (ref "MIX") (pin "1") (pinfunction "1_1") (pintype "passive"))
      (node (ref "R37") (pin "1") (pinfunction "1_1") (pintype "passive"))
    )
    (net (code "58") (name "Net-(Q1-B)") (class "Default")
      (node (ref "Q1") (pin "2") (pinfunction "B_2") (pintype "passive"))
      (node (ref "R16") (pin "1") (pinfunction "1_1") (pintype "passive"))
      (node (ref "R35") (pin "2") (pinfunction "2_2") (pintype "passive"))
    )
    (net (code "59") (name "Net-(Q1-E)") (class "Default")
      (node (ref "Q1") (pin "3") (pinfunction "E_3") (pintype "passive"))
      (node (ref "Q2") (pin "3") (pinfunction "E_3") (pintype "passive"))
      (node (ref "R44") (pin "1") (pinfunction "1_1") (pintype "passive"))
    )
    (net (code "60") (name "Net-(Q3-B)") (class "Default")
      (node (ref "Q3") (pin "2") (pinfunction "B_2") (pintype "passive"))
      (node (ref "R17") (pin "1") (pinfunction "1_1") (pintype "passive"))
      (node (ref "R47") (pin "2") (pinfunction "2_2") (pintype "passive"))
    )
    (net (code "61") (name "Net-(Q3-E)") (class "Default")
      (node (ref "Q3") (pin "3") (pinfunction "E_3") (pintype "passive"))
      (node (ref "Q4") (pin "3") (pinfunction "E_3") (pintype "passive"))
      (node (ref "R46") (pin "1") (pinfunction "1_1") (pintype "passive"))
    )
    (net (code "62") (name "Net-(Q5-B)") (class "Default")
      (node (ref "Q5") (pin "2") (pinfunction "B_2") (pintype "passive"))
      (node (ref "R7") (pin "2") (pinfunction "S_2") (pintype "passive"))
    )
    (net (code "63") (name "Net-(Q5-E)") (class "Default")
      (node (ref "D1") (pin "A") (pinfunction "A_A") (pintype "passive"))
      (node (ref "Q5") (pin "3") (pinfunction "E_3") (pintype "passive"))
      (node (ref "Q6") (pin "3") (pinfunction "E_3") (pintype "passive"))
    )
    (net (code "64") (name "Net-(R4-Pad1)") (class "Default")
      (node (ref "R4") (pin "1") (pinfunction "1_1") (pintype "passive"))
      (node (ref "T_CV") (pin "1") (pinfunction "1_1") (pintype "passive"))
    )
    (net (code "65") (name "Net-(R5-A)") (class "Default")
      (node (ref "C16") (pin "+") (pinfunction "+_+") (pintype "passive"))
      (node (ref "R5") (pin "1") (pinfunction "A_1") (pintype "passive"))
    )
    (net (code "66") (name "Net-(R5-E)") (class "Default")
      (node (ref "C15") (pin "1") (pinfunction "1_1") (pintype "passive"))
      (node (ref "R12") (pin "1") (pinfunction "1_1") (pintype "passive"))
      (node (ref "R13") (pin "1") (pinfunction "1_1") (pintype "passive"))
      (node (ref "R15") (pin "2") (pinfunction "2_2") (pintype "passive"))
      (node (ref "R5") (pin "2") (pinfunction "S_2") (pintype "passive"))
      (node (ref "R5") (pin "3") (pinfunction "E_3") (pintype "passive"))
    )
    (net (code "67") (name "Net-(R6-Pad1)") (class "Default")
      (node (ref "R6") (pin "1") (pinfunction "1_1") (pintype "passive"))
      (node (ref "T_POT") (pin "2") (pinfunction "2_2") (pintype "passive"))
    )
    (net (code "68") (name "Net-(R7-A)") (class "Default")
      (node (ref "R42") (pin "2") (pinfunction "2_2") (pintype "passive"))
      (node (ref "R7") (pin "1") (pinfunction "A_1") (pintype "passive"))
    )
    (net (code "69") (name "Net-(R32-Pad1)") (class "Default")
      (node (ref "R32") (pin "1") (pinfunction "1_1") (pintype "passive"))
      (node (ref "VCA_CV") (pin "1") (pinfunction "1_1") (pintype "passive"))
    )
    (net (code "70") (name "Net-(R33-Pad1)") (class "Default")
      (node (ref "R33") (pin "1") (pinfunction "1_1") (pintype "passive"))
      (node (ref "VCA_POT") (pin "2") (pinfunction "2_2") (pintype "passive"))
    )
    (net (code "71") (name "Net-(R34-Pad2)") (class "Default")
      (node (ref "R34") (pin "2") (pinfunction "2_2") (pintype "passive"))
      (node (ref "WET") (pin "1") (pinfunction "1_1") (pintype "passive"))
    )
    (net (code "72") (name "VCA_CV") (class "Default")
      (node (ref "IC2") (pin "1") (pinfunction "AMPBIAS_1") (pintype "input"))
      (node (ref "Q1") (pin "1") (pinfunction "C_1") (pintype "passive"))
    )
    (net (code "73") (name "unconnected-(IC1-CLOCK-Pad5)") (class "Default")
      (node (ref "IC1") (pin "5") (pinfunction "CLOCK_5") (pintype "output"))
    )
    (net (code "74") (name "unconnected-(IC2B-BUFF_IN-Pad7)") (class "Default")
      (node (ref "IC2") (pin "7") (pinfunction "BUFF_IN_7") (pintype "input"))
    )
    (net (code "75") (name "unconnected-(IC2B-BUFF_OUT-Pad8)") (class "Default")
      (node (ref "IC2") (pin "8") (pinfunction "BUFF_OUT_8") (pintype "bidirectional"))
    )
    (net (code "76") (name "unconnected-(IC2D-BUFF_IN-Pad10)") (class "Default")
      (node (ref "IC2") (pin "10") (pinfunction "BUFF_IN_10") (pintype "input"))
    )
    (net (code "77") (name "unconnected-(IC2D-BUFF_OUT-Pad9)") (class "Default")
      (node (ref "IC2") (pin "9") (pinfunction "BUFF_OUT_9") (pintype "bidirectional"))
    )
  )
)
